# 2018_FDP_SCHEMA.net
KiCad netlist of a schematic drawn in Altium Designer
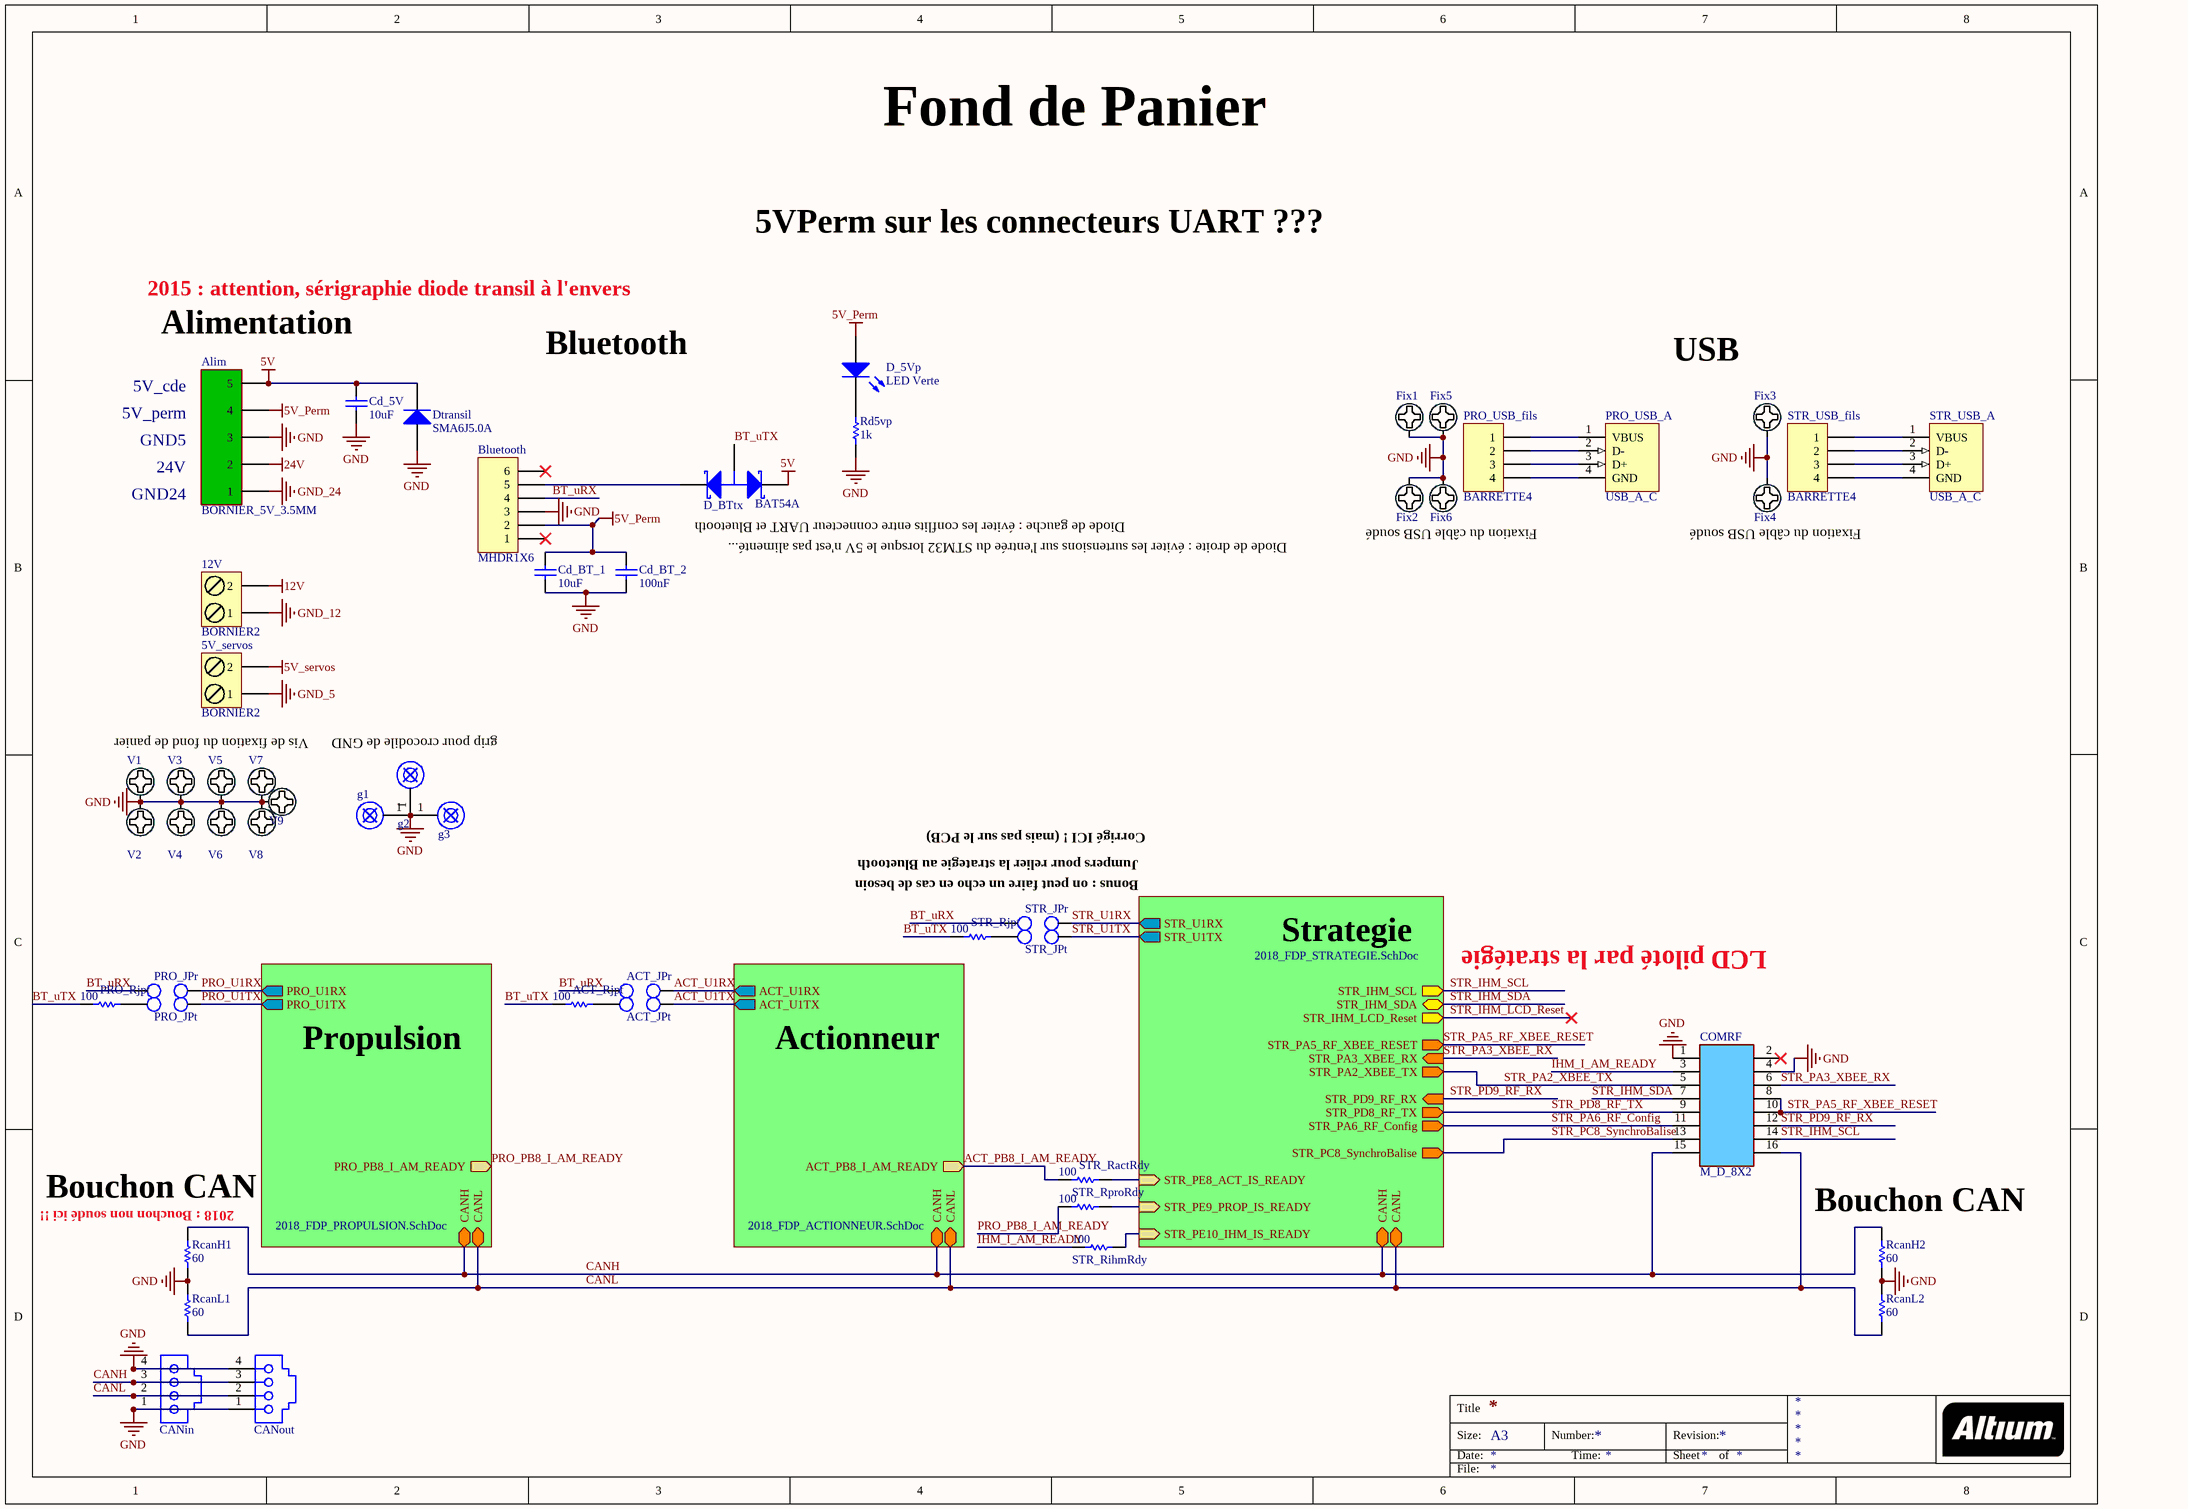
[diagram p0: 2018_FDP_SCHEMA.SchDoc]

(export (version "E")
  (design (tool "Eeschema 10.0.6"))
  (components
    (comp (ref "5V_servos")
      (value "BORNIER2")
      (footprint "BORNIER_2V_5.08MM")
      (description "Terminal blocks, 2 pins, pitch=5mm")
      (libsource (lib "Connecteur") (part "BORNIER2"))
    )
    (comp (ref "12V")
      (value "BORNIER2")
      (footprint "BORNIER_2V_5.08MM")
      (description "Terminal blocks, 2 pins, pitch=5mm")
      (libsource (lib "Connecteur") (part "BORNIER2"))
    )
    (comp (ref "ACT_JPr")
      (value "JUMPER2")
      (footprint "BARRETTE_2_M_D")
      (description "BARRETTE 2 CONTACTS 1 RANGEE MALE DROITE")
      (libsource (lib "connecteurs") (part "JUMPER2"))
    )
    (comp (ref "ACT_JPt")
      (value "JUMPER2")
      (footprint "BARRETTE_2_M_D")
      (description "BARRETTE 2 CONTACTS 1 RANGEE MALE DROITE")
      (libsource (lib "connecteurs") (part "JUMPER2"))
    )
    (comp (ref "ACT_Rjpt")
      (value "100")
      (footprint "R1206_N")
      (description "Resistor")
      (fields (field (name "PUBLISHER") "Altium Limited"))
      (libsource (lib "_ROBOT") (part "Resistor"))
    )
    (comp (ref "Alim")
      (value "BORNIER_5V_3.5MM")
      (footprint "BORNIER_5V_3.5MM_femelle_0")
      (libsource (lib "Connecteur") (part "BORNIER_5V_3.5MM"))
    )
    (comp (ref "Bluetooth")
      (value "MHDR1X6")
      (footprint "HE14_6")
      (description "Header, 6-Pin")
      (fields (field (name "PUBLISHER") "Altium Limited"))
      (libsource (lib "Miscellaneous Connectors") (part "MHDR1X6"))
    )
    (comp (ref "CANin")
      (value "634104149621")
      (footprint "634104149621")
      (description "Modular Jack SMT Vertical Plastic 4P4C Top Entry WR-MJ")
      (fields (field (name "PUBLISHER") "Wurth Elektronik"))
      (libsource (lib "ALTIUM-MJ_VERTICAL_PLASTIC") (part "634104149621"))
    )
    (comp (ref "CANout")
      (value "634104149621")
      (footprint "634104149621")
      (description "Modular Jack SMT Vertical Plastic 4P4C Top Entry WR-MJ")
      (fields (field (name "PUBLISHER") "Wurth Elektronik"))
      (libsource (lib "ALTIUM-MJ_VERTICAL_PLASTIC") (part "634104149621"))
    )
    (comp (ref "Cd_5V")
      (value "10uF")
      (footprint "C1206_N")
      (description "Capacitor")
      (fields (field (name "PUBLISHER") "Altium Limited"))
      (libsource (lib "_ROBOT") (part "Condensateur"))
    )
    (comp (ref "Cd_BT_1")
      (value "10uF")
      (footprint "C1206_N")
      (description "Capacitor")
      (fields (field (name "PUBLISHER") "Altium Limited"))
      (libsource (lib "_ROBOT") (part "Condensateur"))
    )
    (comp (ref "Cd_BT_2")
      (value "100nF")
      (footprint "C0805_N")
      (description "Capacitor")
      (fields (field (name "PUBLISHER") "Altium Limited"))
      (libsource (lib "_ROBOT") (part "Condensateur"))
    )
    (comp (ref "COMRF")
      (value "BARRETTE_8 CONTACTS_2 RANGEES_MALE_DROITE")
      (footprint "HE10/16_M_D_B P")
      (fields (field (name "TYPE") "M_D_8X2"))
      (libsource (lib "connecteurs") (part "BARRETTE_8 CONTACTS_2 RANGEES_MALE_DROITE"))
    )
    (comp (ref "Dtransil")
      (value "SMA6J5.0A")
      (footprint "DO214AC")
      (description "1 Amp General Purpose Rectifier")
      (fields (field (name "PUBLISHER") "Altium Limited"))
      (libsource (lib "Miscellaneous Devices") (part "Diode 1N4001"))
    )
    (comp (ref "D_5Vp")
      (value "LED Verte")
      (footprint "LED_0805")
      (description "Typical LED")
      (fields (field (name "PUBLISHER") "Altium Limited"))
      (libsource (lib "_ROBOT") (part "LED"))
    )
    (comp (ref "D_BTtx")
      (value "BAT54A")
      (footprint "SOT23-3N")
      (description "DIODE SCHOTTKY DOUBLE")
      (fields (field (name "MANUFACTURER") "ZETEX"))
      (libsource (lib "_ROBOT") (part "Diode Shottky double  BAT54A"))
    )
    (comp (ref "Fix1")
      (value "Pad_M3")
      (footprint "Point Test_D3_P1.6mm")
      (description "Vis M3 X 6mm _TORX_Tête 6mm")
      (fields (field (name "PUBLISHER") "Damien Guitton"))
      (libsource (lib "DG_Mecanique") (part "Vis M3 X 6mm _TORX_Tête 6mm"))
    )
    (comp (ref "Fix2")
      (value "Pad_M3")
      (footprint "Point Test_D3_P1.6mm")
      (description "Vis M3 X 6mm _TORX_Tête 6mm")
      (fields (field (name "PUBLISHER") "Damien Guitton"))
      (libsource (lib "DG_Mecanique") (part "Vis M3 X 6mm _TORX_Tête 6mm"))
    )
    (comp (ref "Fix3")
      (value "Pad_M3")
      (footprint "Point Test_D3_P1.6mm")
      (description "Vis M3 X 6mm _TORX_Tête 6mm")
      (fields (field (name "PUBLISHER") "Damien Guitton"))
      (libsource (lib "DG_Mecanique") (part "Vis M3 X 6mm _TORX_Tête 6mm"))
    )
    (comp (ref "Fix4")
      (value "Pad_M3")
      (footprint "Point Test_D3_P1.6mm")
      (description "Vis M3 X 6mm _TORX_Tête 6mm")
      (fields (field (name "PUBLISHER") "Damien Guitton"))
      (libsource (lib "DG_Mecanique") (part "Vis M3 X 6mm _TORX_Tête 6mm"))
    )
    (comp (ref "Fix5")
      (value "Pad_M3")
      (footprint "Point Test_D3_P1.6mm")
      (description "Vis M3 X 6mm _TORX_Tête 6mm")
      (fields (field (name "PUBLISHER") "Damien Guitton"))
      (libsource (lib "DG_Mecanique") (part "Vis M3 X 6mm _TORX_Tête 6mm"))
    )
    (comp (ref "Fix6")
      (value "Pad_M3")
      (footprint "Point Test_D3_P1.6mm")
      (description "Vis M3 X 6mm _TORX_Tête 6mm")
      (fields (field (name "PUBLISHER") "Damien Guitton"))
      (libsource (lib "DG_Mecanique") (part "Vis M3 X 6mm _TORX_Tête 6mm"))
    )
    (comp (ref "g1")
      (value "grip")
      (footprint "POINT_TEST")
      (description "POINT TEST")
      (libsource (lib "connecteurs") (part "POINT_TEST"))
    )
    (comp (ref "g2")
      (value "grip")
      (footprint "POINT_TEST")
      (description "POINT TEST")
      (libsource (lib "connecteurs") (part "POINT_TEST"))
    )
    (comp (ref "g3")
      (value "grip")
      (footprint "POINT_TEST")
      (description "POINT TEST")
      (libsource (lib "connecteurs") (part "POINT_TEST"))
    )
    (comp (ref "PRO_JPr")
      (value "JUMPER2")
      (footprint "BARRETTE_2_M_D")
      (description "BARRETTE 2 CONTACTS 1 RANGEE MALE DROITE")
      (libsource (lib "connecteurs") (part "JUMPER2"))
    )
    (comp (ref "PRO_JPt")
      (value "JUMPER2")
      (footprint "BARRETTE_2_M_D")
      (description "BARRETTE 2 CONTACTS 1 RANGEE MALE DROITE")
      (libsource (lib "connecteurs") (part "JUMPER2"))
    )
    (comp (ref "PRO_Rjpt")
      (value "100")
      (footprint "R1206_N")
      (description "Resistor")
      (fields (field (name "PUBLISHER") "Altium Limited"))
      (libsource (lib "_ROBOT") (part "Resistor"))
    )
    (comp (ref "PRO_USB_A")
      (value "USB_A_COUDEE")
      (footprint "USB_A_C")
      (description "EMBASE USB TRAVERSANTE TYPE A COUDEE")
      (fields (field (name "TYPE") "USB_A_C"))
      (libsource (lib "connecteurs") (part "USB_A_COUDEE"))
    )
    (comp (ref "PRO_USB_fils")
      (value "BARRETTE4")
      (footprint "HE14_4")
      (description "Header, 4-Pin")
      (fields (field (name "PUBLISHER") "Altium Limited"))
      (libsource (lib "Connecteur") (part "BARRETTE4"))
    )
    (comp (ref "RcanH1")
      (value "60")
      (footprint "R1206_N")
      (description "Resistor")
      (fields (field (name "PUBLISHER") "Altium Limited"))
      (libsource (lib "_ROBOT") (part "Resistor"))
    )
    (comp (ref "RcanH2")
      (value "60")
      (footprint "R1206_N")
      (description "Resistor")
      (fields (field (name "PUBLISHER") "Altium Limited"))
      (libsource (lib "_ROBOT") (part "Resistor"))
    )
    (comp (ref "RcanL1")
      (value "60")
      (footprint "R1206_N")
      (description "Resistor")
      (fields (field (name "PUBLISHER") "Altium Limited"))
      (libsource (lib "_ROBOT") (part "Resistor"))
    )
    (comp (ref "RcanL2")
      (value "60")
      (footprint "R1206_N")
      (description "Resistor")
      (fields (field (name "PUBLISHER") "Altium Limited"))
      (libsource (lib "_ROBOT") (part "Resistor"))
    )
    (comp (ref "Rd5vp")
      (value "1k")
      (footprint "R1206_N")
      (description "Resistor")
      (fields (field (name "PUBLISHER") "Altium Limited"))
      (libsource (lib "_ROBOT") (part "Resistor"))
    )
    (comp (ref "STR_JPr")
      (value "JUMPER2")
      (footprint "BARRETTE_2_M_D")
      (description "BARRETTE 2 CONTACTS 1 RANGEE MALE DROITE")
      (libsource (lib "connecteurs") (part "JUMPER2"))
    )
    (comp (ref "STR_JPt")
      (value "JUMPER2")
      (footprint "BARRETTE_2_M_D")
      (description "BARRETTE 2 CONTACTS 1 RANGEE MALE DROITE")
      (libsource (lib "connecteurs") (part "JUMPER2"))
    )
    (comp (ref "STR_RactRdy")
      (value "100")
      (footprint "R1206_N")
      (description "Resistor")
      (fields (field (name "PUBLISHER") "Altium Limited"))
      (libsource (lib "_ROBOT") (part "Resistor"))
    )
    (comp (ref "STR_RihmRdy")
      (value "100")
      (footprint "R1206_N")
      (description "Resistor")
      (fields (field (name "PUBLISHER") "Altium Limited"))
      (libsource (lib "_ROBOT") (part "Resistor"))
    )
    (comp (ref "STR_Rjpt")
      (value "100")
      (footprint "R1206_N")
      (description "Resistor")
      (fields (field (name "PUBLISHER") "Altium Limited"))
      (libsource (lib "_ROBOT") (part "Resistor"))
    )
    (comp (ref "STR_RproRdy")
      (value "100")
      (footprint "R1206_N")
      (description "Resistor")
      (fields (field (name "PUBLISHER") "Altium Limited"))
      (libsource (lib "_ROBOT") (part "Resistor"))
    )
    (comp (ref "STR_USB_A")
      (value "USB_A_COUDEE")
      (footprint "USB_A_C")
      (description "EMBASE USB TRAVERSANTE TYPE A COUDEE")
      (fields (field (name "TYPE") "USB_A_C"))
      (libsource (lib "connecteurs") (part "USB_A_COUDEE"))
    )
    (comp (ref "STR_USB_fils")
      (value "BARRETTE4")
      (footprint "HE14_4")
      (description "Header, 4-Pin")
      (fields (field (name "PUBLISHER") "Altium Limited"))
      (libsource (lib "Connecteur") (part "BARRETTE4"))
    )
    (comp (ref "V1")
      (value "Pad_M3")
      (footprint "M3x6mm Torx")
      (description "Vis M3 X 6mm _TORX_Tête 6mm")
      (fields (field (name "PUBLISHER") "Damien Guitton"))
      (libsource (lib "DG_Mecanique") (part "Vis M3 X 6mm _TORX_Tête 6mm"))
    )
    (comp (ref "V2")
      (value "Pad_M3")
      (footprint "M3x6mm Torx")
      (description "Vis M3 X 6mm _TORX_Tête 6mm")
      (fields (field (name "PUBLISHER") "Damien Guitton"))
      (libsource (lib "DG_Mecanique") (part "Vis M3 X 6mm _TORX_Tête 6mm"))
    )
    (comp (ref "V3")
      (value "Pad_M3")
      (footprint "M3x6mm Torx")
      (description "Vis M3 X 6mm _TORX_Tête 6mm")
      (fields (field (name "PUBLISHER") "Damien Guitton"))
      (libsource (lib "DG_Mecanique") (part "Vis M3 X 6mm _TORX_Tête 6mm"))
    )
    (comp (ref "V4")
      (value "Pad_M3")
      (footprint "M3x6mm Torx")
      (description "Vis M3 X 6mm _TORX_Tête 6mm")
      (fields (field (name "PUBLISHER") "Damien Guitton"))
      (libsource (lib "DG_Mecanique") (part "Vis M3 X 6mm _TORX_Tête 6mm"))
    )
    (comp (ref "V5")
      (value "Pad_M3")
      (footprint "M3x6mm Torx")
      (description "Vis M3 X 6mm _TORX_Tête 6mm")
      (fields (field (name "PUBLISHER") "Damien Guitton"))
      (libsource (lib "DG_Mecanique") (part "Vis M3 X 6mm _TORX_Tête 6mm"))
    )
    (comp (ref "V6")
      (value "Pad_M3")
      (footprint "M3x6mm Torx")
      (description "Vis M3 X 6mm _TORX_Tête 6mm")
      (fields (field (name "PUBLISHER") "Damien Guitton"))
      (libsource (lib "DG_Mecanique") (part "Vis M3 X 6mm _TORX_Tête 6mm"))
    )
    (comp (ref "V7")
      (value "Pad_M3")
      (footprint "M3x6mm Torx")
      (description "Vis M3 X 6mm _TORX_Tête 6mm")
      (fields (field (name "PUBLISHER") "Damien Guitton"))
      (libsource (lib "DG_Mecanique") (part "Vis M3 X 6mm _TORX_Tête 6mm"))
    )
    (comp (ref "V8")
      (value "Pad_M3")
      (footprint "M3x6mm Torx")
      (description "Vis M3 X 6mm _TORX_Tête 6mm")
      (fields (field (name "PUBLISHER") "Damien Guitton"))
      (libsource (lib "DG_Mecanique") (part "Vis M3 X 6mm _TORX_Tête 6mm"))
    )
    (comp (ref "V9")
      (value "Pad_M3")
      (footprint "M3x6mm Torx")
      (description "Vis M3 X 6mm _TORX_Tête 6mm")
      (fields (field (name "PUBLISHER") "Damien Guitton"))
      (libsource (lib "DG_Mecanique") (part "Vis M3 X 6mm _TORX_Tête 6mm"))
    )
  )
  (nets
    (net (code "1") (name "/ACT_PB8_I_AM_READY") (class "Default")
      (node (ref "STR_RactRdy") (pin "2") (pinfunction "2_2") (pintype "passive"))
    )
    (net (code "2") (name "/ACT_U1RX") (class "Default")
      (node (ref "ACT_JPr") (pin "2") (pinfunction "2_2") (pintype "passive"))
    )
    (net (code "3") (name "/ACT_U1TX") (class "Default")
      (node (ref "ACT_JPt") (pin "2") (pinfunction "2_2") (pintype "passive"))
    )
    (net (code "4") (name "/BT_uRX") (class "Default")
      (node (ref "ACT_JPr") (pin "1") (pinfunction "1_1") (pintype "passive"))
      (node (ref "Bluetooth") (pin "4") (pinfunction "4_4") (pintype "passive"))
      (node (ref "PRO_JPr") (pin "1") (pinfunction "1_1") (pintype "passive"))
      (node (ref "STR_JPr") (pin "1") (pinfunction "1_1") (pintype "passive"))
    )
    (net (code "5") (name "/BT_uTX") (class "Default")
      (node (ref "ACT_Rjpt") (pin "2") (pinfunction "2_2") (pintype "passive"))
      (node (ref "D_BTtx") (pin "3") (pinfunction "A_3") (pintype "passive"))
      (node (ref "PRO_Rjpt") (pin "2") (pinfunction "2_2") (pintype "passive"))
      (node (ref "STR_Rjpt") (pin "2") (pinfunction "2_2") (pintype "passive"))
    )
    (net (code "6") (name "/CANH") (class "Default")
      (node (ref "CANin") (pin "3") (pinfunction "3_3") (pintype "passive"))
      (node (ref "CANout") (pin "3") (pinfunction "3_3") (pintype "passive"))
      (node (ref "COMRF") (pin "15") (pinfunction "15_15") (pintype "passive"))
      (node (ref "RcanH1") (pin "2") (pinfunction "2_2") (pintype "passive"))
      (node (ref "RcanH2") (pin "1") (pinfunction "1_1") (pintype "passive"))
    )
    (net (code "7") (name "/CANL") (class "Default")
      (node (ref "CANin") (pin "2") (pinfunction "2_2") (pintype "passive"))
      (node (ref "CANout") (pin "2") (pinfunction "2_2") (pintype "passive"))
      (node (ref "COMRF") (pin "16") (pinfunction "16_16") (pintype "passive"))
      (node (ref "RcanL1") (pin "1") (pinfunction "1_1") (pintype "passive"))
      (node (ref "RcanL2") (pin "1") (pinfunction "1_1") (pintype "passive"))
    )
    (net (code "8") (name "/IHM_I_AM_READY") (class "Default")
      (node (ref "COMRF") (pin "3") (pinfunction "3_3") (pintype "passive"))
      (node (ref "STR_RihmRdy") (pin "2") (pinfunction "2_2") (pintype "passive"))
    )
    (net (code "9") (name "/PRO_PB8_I_AM_READY") (class "Default")
      (node (ref "STR_RproRdy") (pin "2") (pinfunction "2_2") (pintype "passive"))
    )
    (net (code "10") (name "/PRO_U1RX") (class "Default")
      (node (ref "PRO_JPr") (pin "2") (pinfunction "2_2") (pintype "passive"))
    )
    (net (code "11") (name "/PRO_U1TX") (class "Default")
      (node (ref "PRO_JPt") (pin "2") (pinfunction "2_2") (pintype "passive"))
    )
    (net (code "13") (name "/STR_IHM_SCL") (class "Default")
      (node (ref "COMRF") (pin "14") (pinfunction "14_14") (pintype "passive"))
    )
    (net (code "14") (name "/STR_IHM_SDA") (class "Default")
      (node (ref "COMRF") (pin "7") (pinfunction "7_7") (pintype "passive"))
    )
    (net (code "15") (name "/STR_PA2_XBEE_TX") (class "Default")
      (node (ref "COMRF") (pin "5") (pinfunction "5_5") (pintype "passive"))
    )
    (net (code "16") (name "/STR_PA3_XBEE_RX") (class "Default")
      (node (ref "COMRF") (pin "6") (pinfunction "6_6") (pintype "passive"))
    )
    (net (code "17") (name "/STR_PA5_RF_XBEE_RESET") (class "Default")
      (node (ref "COMRF") (pin "10") (pinfunction "10_10") (pintype "passive"))
      (node (ref "COMRF") (pin "8") (pinfunction "8_8") (pintype "passive"))
    )
    (net (code "18") (name "/STR_PA6_RF_Config") (class "Default")
      (node (ref "COMRF") (pin "11") (pinfunction "11_11") (pintype "passive"))
    )
    (net (code "19") (name "/STR_PC8_SynchroBalise") (class "Default")
      (node (ref "COMRF") (pin "13") (pinfunction "13_13") (pintype "passive"))
    )
    (net (code "20") (name "/STR_PD8_RF_TX") (class "Default")
      (node (ref "COMRF") (pin "9") (pinfunction "9_9") (pintype "passive"))
    )
    (net (code "21") (name "/STR_PD9_RF_RX") (class "Default")
      (node (ref "COMRF") (pin "12") (pinfunction "12_12") (pintype "passive"))
    )
    (net (code "22") (name "/STR_PE8_ACT_IS_READY") (class "Default")
      (node (ref "STR_RactRdy") (pin "1") (pinfunction "1_1") (pintype "passive"))
    )
    (net (code "23") (name "/STR_PE9_PROP_IS_READY") (class "Default")
      (node (ref "STR_RproRdy") (pin "1") (pinfunction "1_1") (pintype "passive"))
    )
    (net (code "24") (name "/STR_PE10_IHM_IS_READY") (class "Default")
      (node (ref "STR_RihmRdy") (pin "1") (pinfunction "1_1") (pintype "passive"))
    )
    (net (code "25") (name "/STR_U1RX") (class "Default")
      (node (ref "STR_JPr") (pin "2") (pinfunction "2_2") (pintype "passive"))
    )
    (net (code "26") (name "/STR_U1TX") (class "Default")
      (node (ref "STR_JPt") (pin "2") (pinfunction "2_2") (pintype "passive"))
    )
    (net (code "27") (name "5V") (class "Default")
      (node (ref "Alim") (pin "5") (pinfunction "5_5") (pintype "passive"))
      (node (ref "Cd_5V") (pin "2") (pinfunction "2_2") (pintype "passive"))
      (node (ref "D_BTtx") (pin "2") (pinfunction "K2_2") (pintype "passive"))
      (node (ref "Dtransil") (pin "2") (pinfunction "K_2") (pintype "passive"))
    )
    (net (code "28") (name "5V_Perm") (class "Default")
      (node (ref "Alim") (pin "4") (pinfunction "4_4") (pintype "passive"))
      (node (ref "Bluetooth") (pin "2") (pinfunction "2_2") (pintype "passive"))
      (node (ref "Cd_BT_1") (pin "2") (pinfunction "2_2") (pintype "passive"))
      (node (ref "Cd_BT_2") (pin "2") (pinfunction "2_2") (pintype "passive"))
      (node (ref "D_5Vp") (pin "1") (pinfunction "A_1") (pintype "passive"))
    )
    (net (code "29") (name "5V_servos") (class "Default")
      (node (ref "5V_servos") (pin "2") (pinfunction "2_2") (pintype "passive"))
    )
    (net (code "30") (name "12V") (class "Default")
      (node (ref "12V") (pin "2") (pinfunction "2_2") (pintype "passive"))
    )
    (net (code "31") (name "24V") (class "Default")
      (node (ref "Alim") (pin "2") (pinfunction "2_2") (pintype "passive"))
    )
    (net (code "32") (name "GND") (class "Default")
      (node (ref "Alim") (pin "3") (pinfunction "3_3") (pintype "passive"))
      (node (ref "Bluetooth") (pin "3") (pinfunction "3_3") (pintype "passive"))
      (node (ref "CANin") (pin "1") (pinfunction "1_1") (pintype "passive"))
      (node (ref "CANin") (pin "4") (pinfunction "4_4") (pintype "passive"))
      (node (ref "CANout") (pin "1") (pinfunction "1_1") (pintype "passive"))
      (node (ref "CANout") (pin "4") (pinfunction "4_4") (pintype "passive"))
      (node (ref "COMRF") (pin "1") (pinfunction "1_1") (pintype "passive"))
      (node (ref "COMRF") (pin "4") (pinfunction "4_4") (pintype "passive"))
      (node (ref "Cd_5V") (pin "1") (pinfunction "1_1") (pintype "passive"))
      (node (ref "Cd_BT_1") (pin "1") (pinfunction "1_1") (pintype "passive"))
      (node (ref "Cd_BT_2") (pin "1") (pinfunction "1_1") (pintype "passive"))
      (node (ref "Dtransil") (pin "1") (pinfunction "A_1") (pintype "passive"))
      (node (ref "Fix1") (pin "1") (pinfunction "1_1") (pintype "passive"))
      (node (ref "Fix2") (pin "1") (pinfunction "1_1") (pintype "passive"))
      (node (ref "Fix3") (pin "1") (pinfunction "1_1") (pintype "passive"))
      (node (ref "Fix4") (pin "1") (pinfunction "1_1") (pintype "passive"))
      (node (ref "Fix5") (pin "1") (pinfunction "1_1") (pintype "passive"))
      (node (ref "Fix6") (pin "1") (pinfunction "1_1") (pintype "passive"))
      (node (ref "RcanH1") (pin "1") (pinfunction "1_1") (pintype "passive"))
      (node (ref "RcanH2") (pin "2") (pinfunction "2_2") (pintype "passive"))
      (node (ref "RcanL1") (pin "2") (pinfunction "2_2") (pintype "passive"))
      (node (ref "RcanL2") (pin "2") (pinfunction "2_2") (pintype "passive"))
      (node (ref "Rd5vp") (pin "2") (pinfunction "2_2") (pintype "passive"))
      (node (ref "V1") (pin "1") (pinfunction "1_1") (pintype "passive"))
      (node (ref "V2") (pin "1") (pinfunction "1_1") (pintype "passive"))
      (node (ref "V3") (pin "1") (pinfunction "1_1") (pintype "passive"))
      (node (ref "V4") (pin "1") (pinfunction "1_1") (pintype "passive"))
      (node (ref "V5") (pin "1") (pinfunction "1_1") (pintype "passive"))
      (node (ref "V6") (pin "1") (pinfunction "1_1") (pintype "passive"))
      (node (ref "V7") (pin "1") (pinfunction "1_1") (pintype "passive"))
      (node (ref "V8") (pin "1") (pinfunction "1_1") (pintype "passive"))
      (node (ref "V9") (pin "1") (pinfunction "1_1") (pintype "passive"))
      (node (ref "g1") (pin "1") (pinfunction "3_1") (pintype "passive"))
      (node (ref "g2") (pin "1") (pinfunction "3_1") (pintype "passive"))
      (node (ref "g3") (pin "1") (pinfunction "3_1") (pintype "passive"))
    )
    (net (code "33") (name "GND_5") (class "Default")
      (node (ref "5V_servos") (pin "1") (pinfunction "1_1") (pintype "passive"))
    )
    (net (code "34") (name "GND_12") (class "Default")
      (node (ref "12V") (pin "1") (pinfunction "1_1") (pintype "passive"))
    )
    (net (code "35") (name "GND_24") (class "Default")
      (node (ref "Alim") (pin "1") (pinfunction "1_1") (pintype "passive"))
    )
    (net (code "36") (name "Net-(ACT_JPt-Pad1)") (class "Default")
      (node (ref "ACT_JPt") (pin "1") (pinfunction "1_1") (pintype "passive"))
      (node (ref "ACT_Rjpt") (pin "1") (pinfunction "1_1") (pintype "passive"))
    )
    (net (code "37") (name "Net-(D_5Vp-K)") (class "Default")
      (node (ref "D_5Vp") (pin "2") (pinfunction "K_2") (pintype "passive"))
      (node (ref "Rd5vp") (pin "1") (pinfunction "1_1") (pintype "passive"))
    )
    (net (code "38") (name "Net-(D_BTtx-K1)") (class "Default")
      (node (ref "Bluetooth") (pin "5") (pinfunction "5_5") (pintype "passive"))
      (node (ref "D_BTtx") (pin "1") (pinfunction "K1_1") (pintype "passive"))
    )
    (net (code "39") (name "Net-(PRO_JPt-Pad1)") (class "Default")
      (node (ref "PRO_JPt") (pin "1") (pinfunction "1_1") (pintype "passive"))
      (node (ref "PRO_Rjpt") (pin "1") (pinfunction "1_1") (pintype "passive"))
    )
    (net (code "40") (name "Net-(PRO_USB_A-D+)") (class "Default")
      (node (ref "PRO_USB_A") (pin "3") (pinfunction "D+_3") (pintype "input"))
      (node (ref "PRO_USB_fils") (pin "3") (pinfunction "3_3") (pintype "passive"))
    )
    (net (code "41") (name "Net-(PRO_USB_A-D-)") (class "Default")
      (node (ref "PRO_USB_A") (pin "2") (pinfunction "D-_2") (pintype "input"))
      (node (ref "PRO_USB_fils") (pin "2") (pinfunction "2_2") (pintype "passive"))
    )
    (net (code "42") (name "Net-(PRO_USB_A-GND)") (class "Default")
      (node (ref "PRO_USB_A") (pin "4") (pinfunction "GND_4") (pintype "power_in"))
      (node (ref "PRO_USB_fils") (pin "4") (pinfunction "4_4") (pintype "passive"))
    )
    (net (code "43") (name "Net-(PRO_USB_A-VBUS)") (class "Default")
      (node (ref "PRO_USB_A") (pin "1") (pinfunction "VBUS_1") (pintype "power_in"))
      (node (ref "PRO_USB_fils") (pin "1") (pinfunction "1_1") (pintype "passive"))
    )
    (net (code "44") (name "Net-(STR_JPt-Pad1)") (class "Default")
      (node (ref "STR_JPt") (pin "1") (pinfunction "1_1") (pintype "passive"))
      (node (ref "STR_Rjpt") (pin "1") (pinfunction "1_1") (pintype "passive"))
    )
    (net (code "45") (name "Net-(STR_USB_A-D+)") (class "Default")
      (node (ref "STR_USB_A") (pin "3") (pinfunction "D+_3") (pintype "input"))
      (node (ref "STR_USB_fils") (pin "3") (pinfunction "3_3") (pintype "passive"))
    )
    (net (code "46") (name "Net-(STR_USB_A-D-)") (class "Default")
      (node (ref "STR_USB_A") (pin "2") (pinfunction "D-_2") (pintype "input"))
      (node (ref "STR_USB_fils") (pin "2") (pinfunction "2_2") (pintype "passive"))
    )
    (net (code "47") (name "Net-(STR_USB_A-GND)") (class "Default")
      (node (ref "STR_USB_A") (pin "4") (pinfunction "GND_4") (pintype "power_in"))
      (node (ref "STR_USB_fils") (pin "4") (pinfunction "4_4") (pintype "passive"))
    )
    (net (code "48") (name "Net-(STR_USB_A-VBUS)") (class "Default")
      (node (ref "STR_USB_A") (pin "1") (pinfunction "VBUS_1") (pintype "power_in"))
      (node (ref "STR_USB_fils") (pin "1") (pinfunction "1_1") (pintype "passive"))
    )
    (net (code "49") (name "unconnected-(Bluetooth-Pad1)") (class "Default")
      (node (ref "Bluetooth") (pin "1") (pinfunction "1_1") (pintype "passive+no_connect"))
    )
    (net (code "50") (name "unconnected-(Bluetooth-Pad6)") (class "Default")
      (node (ref "Bluetooth") (pin "6") (pinfunction "6_6") (pintype "passive+no_connect"))
    )
    (net (code "51") (name "unconnected-(COMRF-Pad2)") (class "Default")
      (node (ref "COMRF") (pin "2") (pinfunction "2_2") (pintype "passive+no_connect"))
    )
  )
)
